# rel-ram-4x8K.net
KiCad netlist of a schematic drawn in EAGLE
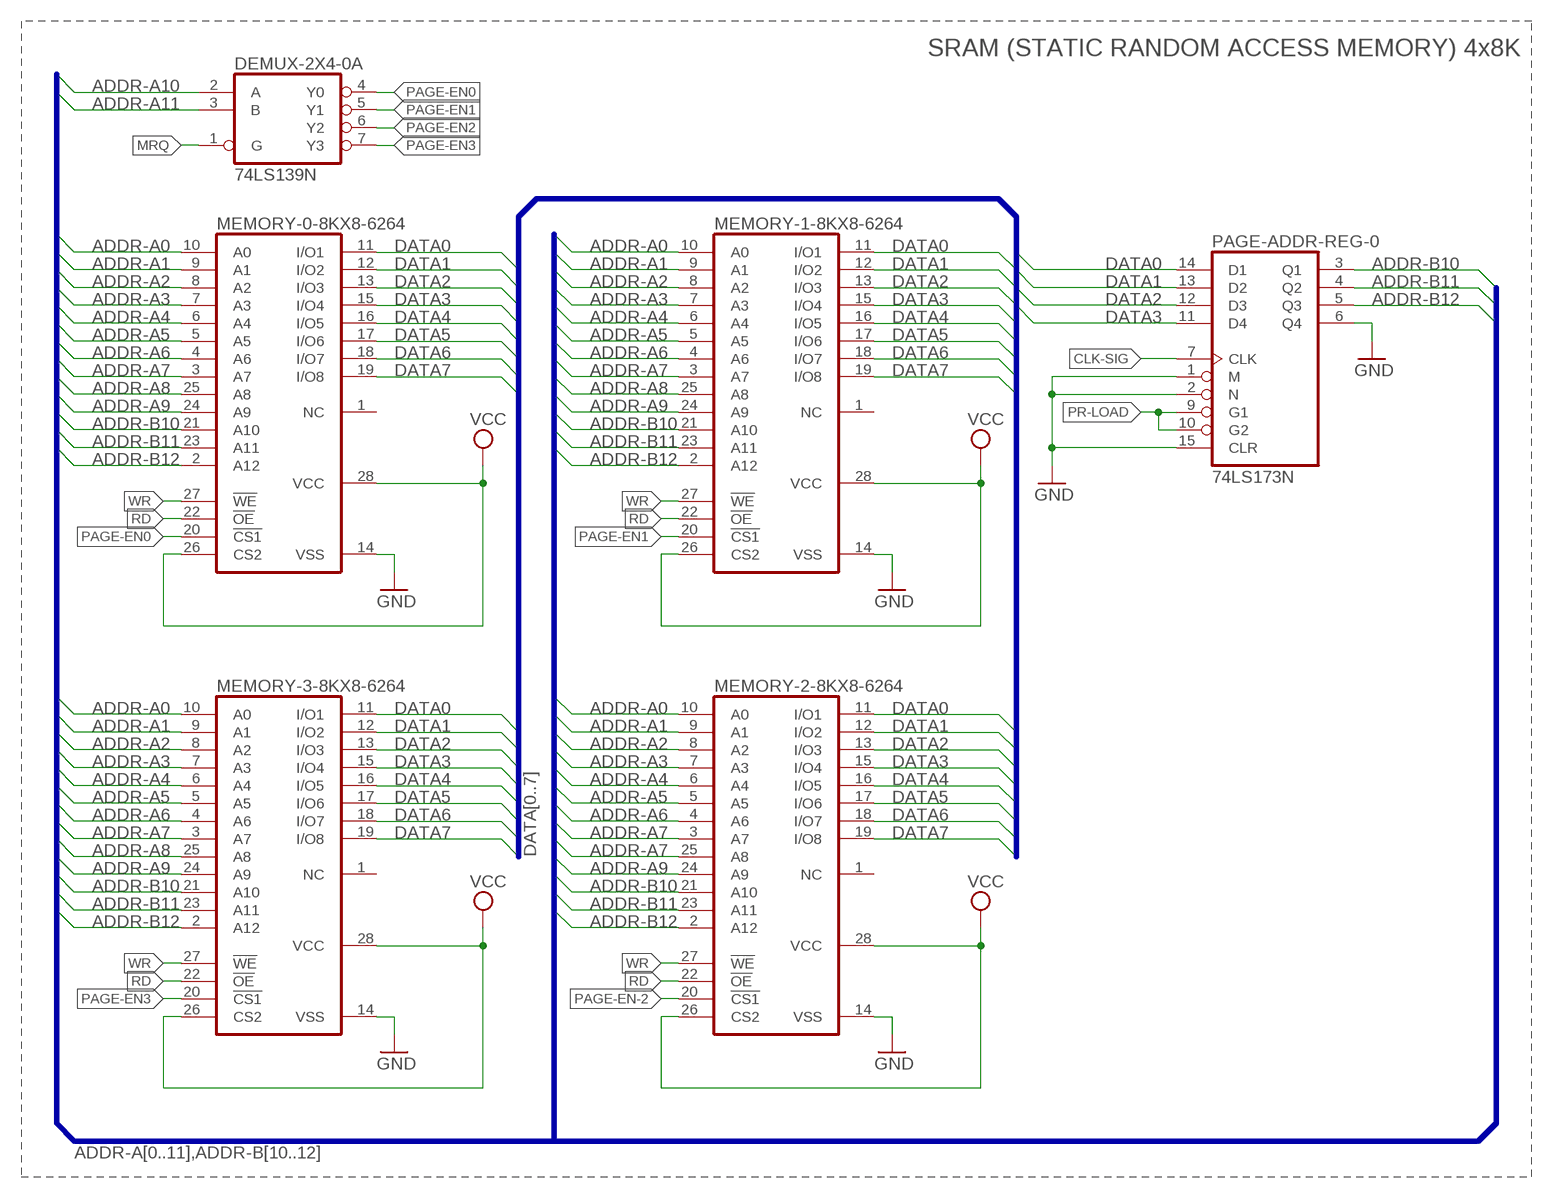
[diagram p0: schematic, sheet 1]

(export (version "E")
  (design (tool "Eeschema 10.0.6"))
  (components
    (comp (ref "DEMUX-2X4-0")
      (value "74LS139N")
      (footprint "eagle-import:DIL16")
      (libsource (lib "eagle-import") (part "74139NLS"))
    )
    (comp (ref "MEMORY-0-8KX8-6264")
      (value "6264A")
      (footprint "eagle-import:DIL28-6")
      (libsource (lib "eagle-import") (part "6264A"))
    )
    (comp (ref "MEMORY-1-8KX8-6264")
      (value "6264A")
      (footprint "eagle-import:DIL28-6")
      (libsource (lib "eagle-import") (part "6264A"))
    )
    (comp (ref "MEMORY-2-8KX8-6264")
      (value "6264A")
      (footprint "eagle-import:DIL28-6")
      (libsource (lib "eagle-import") (part "6264A"))
    )
    (comp (ref "MEMORY-3-8KX8-6264")
      (value "6264A")
      (footprint "eagle-import:DIL28-6")
      (libsource (lib "eagle-import") (part "6264A"))
    )
    (comp (ref "PAGE-ADDR-REG-0")
      (value "74LS173N")
      (footprint "eagle-import:DIL16")
      (libsource (lib "eagle-import") (part "74173NLS"))
    )
  )
  (nets
    (net (code "1") (name "/ADDR-A0") (class "Default")
      (node (ref "MEMORY-0-8KX8-6264") (pin "10") (pinfunction "A0_10") (pintype "input"))
      (node (ref "MEMORY-1-8KX8-6264") (pin "10") (pinfunction "A0_10") (pintype "input"))
      (node (ref "MEMORY-2-8KX8-6264") (pin "10") (pinfunction "A0_10") (pintype "input"))
      (node (ref "MEMORY-3-8KX8-6264") (pin "10") (pinfunction "A0_10") (pintype "input"))
    )
    (net (code "2") (name "/ADDR-A1") (class "Default")
      (node (ref "MEMORY-0-8KX8-6264") (pin "9") (pinfunction "A1_9") (pintype "input"))
      (node (ref "MEMORY-1-8KX8-6264") (pin "9") (pinfunction "A1_9") (pintype "input"))
      (node (ref "MEMORY-2-8KX8-6264") (pin "9") (pinfunction "A1_9") (pintype "input"))
      (node (ref "MEMORY-3-8KX8-6264") (pin "9") (pinfunction "A1_9") (pintype "input"))
    )
    (net (code "3") (name "/ADDR-A2") (class "Default")
      (node (ref "MEMORY-0-8KX8-6264") (pin "8") (pinfunction "A2_8") (pintype "input"))
      (node (ref "MEMORY-1-8KX8-6264") (pin "8") (pinfunction "A2_8") (pintype "input"))
      (node (ref "MEMORY-2-8KX8-6264") (pin "8") (pinfunction "A2_8") (pintype "input"))
      (node (ref "MEMORY-3-8KX8-6264") (pin "8") (pinfunction "A2_8") (pintype "input"))
    )
    (net (code "4") (name "/ADDR-A3") (class "Default")
      (node (ref "MEMORY-0-8KX8-6264") (pin "7") (pinfunction "A3_7") (pintype "input"))
      (node (ref "MEMORY-1-8KX8-6264") (pin "7") (pinfunction "A3_7") (pintype "input"))
      (node (ref "MEMORY-2-8KX8-6264") (pin "7") (pinfunction "A3_7") (pintype "input"))
      (node (ref "MEMORY-3-8KX8-6264") (pin "7") (pinfunction "A3_7") (pintype "input"))
    )
    (net (code "5") (name "/ADDR-A4") (class "Default")
      (node (ref "MEMORY-0-8KX8-6264") (pin "6") (pinfunction "A4_6") (pintype "input"))
      (node (ref "MEMORY-1-8KX8-6264") (pin "6") (pinfunction "A4_6") (pintype "input"))
      (node (ref "MEMORY-2-8KX8-6264") (pin "6") (pinfunction "A4_6") (pintype "input"))
      (node (ref "MEMORY-3-8KX8-6264") (pin "6") (pinfunction "A4_6") (pintype "input"))
    )
    (net (code "6") (name "/ADDR-A5") (class "Default")
      (node (ref "MEMORY-0-8KX8-6264") (pin "5") (pinfunction "A5_5") (pintype "input"))
      (node (ref "MEMORY-1-8KX8-6264") (pin "5") (pinfunction "A5_5") (pintype "input"))
      (node (ref "MEMORY-2-8KX8-6264") (pin "5") (pinfunction "A5_5") (pintype "input"))
      (node (ref "MEMORY-3-8KX8-6264") (pin "5") (pinfunction "A5_5") (pintype "input"))
    )
    (net (code "7") (name "/ADDR-A6") (class "Default")
      (node (ref "MEMORY-0-8KX8-6264") (pin "4") (pinfunction "A6_4") (pintype "input"))
      (node (ref "MEMORY-1-8KX8-6264") (pin "4") (pinfunction "A6_4") (pintype "input"))
      (node (ref "MEMORY-2-8KX8-6264") (pin "4") (pinfunction "A6_4") (pintype "input"))
      (node (ref "MEMORY-3-8KX8-6264") (pin "4") (pinfunction "A6_4") (pintype "input"))
    )
    (net (code "8") (name "/ADDR-A7") (class "Default")
      (node (ref "MEMORY-0-8KX8-6264") (pin "3") (pinfunction "A7_3") (pintype "input"))
      (node (ref "MEMORY-1-8KX8-6264") (pin "3") (pinfunction "A7_3") (pintype "input"))
      (node (ref "MEMORY-2-8KX8-6264") (pin "25") (pinfunction "A8_25") (pintype "input"))
      (node (ref "MEMORY-2-8KX8-6264") (pin "3") (pinfunction "A7_3") (pintype "input"))
      (node (ref "MEMORY-3-8KX8-6264") (pin "3") (pinfunction "A7_3") (pintype "input"))
    )
    (net (code "9") (name "/ADDR-A8") (class "Default")
      (node (ref "MEMORY-0-8KX8-6264") (pin "25") (pinfunction "A8_25") (pintype "input"))
      (node (ref "MEMORY-1-8KX8-6264") (pin "25") (pinfunction "A8_25") (pintype "input"))
      (node (ref "MEMORY-3-8KX8-6264") (pin "25") (pinfunction "A8_25") (pintype "input"))
    )
    (net (code "10") (name "/ADDR-A9") (class "Default")
      (node (ref "MEMORY-0-8KX8-6264") (pin "24") (pinfunction "A9_24") (pintype "input"))
      (node (ref "MEMORY-1-8KX8-6264") (pin "24") (pinfunction "A9_24") (pintype "input"))
      (node (ref "MEMORY-2-8KX8-6264") (pin "24") (pinfunction "A9_24") (pintype "input"))
      (node (ref "MEMORY-3-8KX8-6264") (pin "24") (pinfunction "A9_24") (pintype "input"))
    )
    (net (code "11") (name "/ADDR-A10") (class "Default")
      (node (ref "DEMUX-2X4-0") (pin "2") (pinfunction "A_2") (pintype "input"))
    )
    (net (code "12") (name "/ADDR-A11") (class "Default")
      (node (ref "DEMUX-2X4-0") (pin "3") (pinfunction "B_3") (pintype "input"))
    )
    (net (code "13") (name "/ADDR-B10") (class "Default")
      (node (ref "MEMORY-0-8KX8-6264") (pin "21") (pinfunction "A10_21") (pintype "input"))
      (node (ref "MEMORY-1-8KX8-6264") (pin "21") (pinfunction "A10_21") (pintype "input"))
      (node (ref "MEMORY-2-8KX8-6264") (pin "21") (pinfunction "A10_21") (pintype "input"))
      (node (ref "MEMORY-3-8KX8-6264") (pin "21") (pinfunction "A10_21") (pintype "input"))
      (node (ref "PAGE-ADDR-REG-0") (pin "3") (pinfunction "Q1_3") (pintype "tri_state"))
    )
    (net (code "14") (name "/ADDR-B11") (class "Default")
      (node (ref "MEMORY-0-8KX8-6264") (pin "23") (pinfunction "A11_23") (pintype "input"))
      (node (ref "MEMORY-1-8KX8-6264") (pin "23") (pinfunction "A11_23") (pintype "input"))
      (node (ref "MEMORY-2-8KX8-6264") (pin "23") (pinfunction "A11_23") (pintype "input"))
      (node (ref "MEMORY-3-8KX8-6264") (pin "23") (pinfunction "A11_23") (pintype "input"))
      (node (ref "PAGE-ADDR-REG-0") (pin "4") (pinfunction "Q2_4") (pintype "tri_state"))
    )
    (net (code "15") (name "/ADDR-B12") (class "Default")
      (node (ref "MEMORY-0-8KX8-6264") (pin "2") (pinfunction "A12_2") (pintype "input"))
      (node (ref "MEMORY-1-8KX8-6264") (pin "2") (pinfunction "A12_2") (pintype "input"))
      (node (ref "MEMORY-2-8KX8-6264") (pin "2") (pinfunction "A12_2") (pintype "input"))
      (node (ref "MEMORY-3-8KX8-6264") (pin "2") (pinfunction "A12_2") (pintype "input"))
      (node (ref "PAGE-ADDR-REG-0") (pin "5") (pinfunction "Q3_5") (pintype "tri_state"))
    )
    (net (code "16") (name "/DATA0") (class "Default")
      (node (ref "MEMORY-0-8KX8-6264") (pin "11") (pinfunction "I/O1_11") (pintype "bidirectional"))
      (node (ref "MEMORY-1-8KX8-6264") (pin "11") (pinfunction "I/O1_11") (pintype "bidirectional"))
      (node (ref "MEMORY-2-8KX8-6264") (pin "11") (pinfunction "I/O1_11") (pintype "bidirectional"))
      (node (ref "MEMORY-3-8KX8-6264") (pin "11") (pinfunction "I/O1_11") (pintype "bidirectional"))
      (node (ref "PAGE-ADDR-REG-0") (pin "14") (pinfunction "D1_14") (pintype "input"))
    )
    (net (code "17") (name "/DATA1") (class "Default")
      (node (ref "MEMORY-0-8KX8-6264") (pin "12") (pinfunction "I/O2_12") (pintype "bidirectional"))
      (node (ref "MEMORY-1-8KX8-6264") (pin "12") (pinfunction "I/O2_12") (pintype "bidirectional"))
      (node (ref "MEMORY-2-8KX8-6264") (pin "12") (pinfunction "I/O2_12") (pintype "bidirectional"))
      (node (ref "MEMORY-3-8KX8-6264") (pin "12") (pinfunction "I/O2_12") (pintype "bidirectional"))
      (node (ref "PAGE-ADDR-REG-0") (pin "13") (pinfunction "D2_13") (pintype "input"))
    )
    (net (code "18") (name "/DATA2") (class "Default")
      (node (ref "MEMORY-0-8KX8-6264") (pin "13") (pinfunction "I/O3_13") (pintype "bidirectional"))
      (node (ref "MEMORY-1-8KX8-6264") (pin "13") (pinfunction "I/O3_13") (pintype "bidirectional"))
      (node (ref "MEMORY-2-8KX8-6264") (pin "13") (pinfunction "I/O3_13") (pintype "bidirectional"))
      (node (ref "MEMORY-3-8KX8-6264") (pin "13") (pinfunction "I/O3_13") (pintype "bidirectional"))
      (node (ref "PAGE-ADDR-REG-0") (pin "12") (pinfunction "D3_12") (pintype "input"))
    )
    (net (code "19") (name "/DATA3") (class "Default")
      (node (ref "MEMORY-0-8KX8-6264") (pin "15") (pinfunction "I/O4_15") (pintype "bidirectional"))
      (node (ref "MEMORY-1-8KX8-6264") (pin "15") (pinfunction "I/O4_15") (pintype "bidirectional"))
      (node (ref "MEMORY-2-8KX8-6264") (pin "15") (pinfunction "I/O4_15") (pintype "bidirectional"))
      (node (ref "MEMORY-3-8KX8-6264") (pin "15") (pinfunction "I/O4_15") (pintype "bidirectional"))
      (node (ref "PAGE-ADDR-REG-0") (pin "11") (pinfunction "D4_11") (pintype "input"))
    )
    (net (code "20") (name "/DATA4") (class "Default")
      (node (ref "MEMORY-0-8KX8-6264") (pin "16") (pinfunction "I/O5_16") (pintype "bidirectional"))
      (node (ref "MEMORY-1-8KX8-6264") (pin "16") (pinfunction "I/O5_16") (pintype "bidirectional"))
      (node (ref "MEMORY-2-8KX8-6264") (pin "16") (pinfunction "I/O5_16") (pintype "bidirectional"))
      (node (ref "MEMORY-3-8KX8-6264") (pin "16") (pinfunction "I/O5_16") (pintype "bidirectional"))
    )
    (net (code "21") (name "/DATA5") (class "Default")
      (node (ref "MEMORY-0-8KX8-6264") (pin "17") (pinfunction "I/O6_17") (pintype "bidirectional"))
      (node (ref "MEMORY-1-8KX8-6264") (pin "17") (pinfunction "I/O6_17") (pintype "bidirectional"))
      (node (ref "MEMORY-2-8KX8-6264") (pin "17") (pinfunction "I/O6_17") (pintype "bidirectional"))
      (node (ref "MEMORY-3-8KX8-6264") (pin "17") (pinfunction "I/O6_17") (pintype "bidirectional"))
    )
    (net (code "22") (name "/DATA6") (class "Default")
      (node (ref "MEMORY-0-8KX8-6264") (pin "18") (pinfunction "I/O7_18") (pintype "bidirectional"))
      (node (ref "MEMORY-1-8KX8-6264") (pin "18") (pinfunction "I/O7_18") (pintype "bidirectional"))
      (node (ref "MEMORY-2-8KX8-6264") (pin "18") (pinfunction "I/O7_18") (pintype "bidirectional"))
      (node (ref "MEMORY-3-8KX8-6264") (pin "18") (pinfunction "I/O7_18") (pintype "bidirectional"))
    )
    (net (code "23") (name "/DATA7") (class "Default")
      (node (ref "MEMORY-0-8KX8-6264") (pin "19") (pinfunction "I/O8_19") (pintype "bidirectional"))
      (node (ref "MEMORY-1-8KX8-6264") (pin "19") (pinfunction "I/O8_19") (pintype "bidirectional"))
      (node (ref "MEMORY-2-8KX8-6264") (pin "19") (pinfunction "I/O8_19") (pintype "bidirectional"))
      (node (ref "MEMORY-3-8KX8-6264") (pin "19") (pinfunction "I/O8_19") (pintype "bidirectional"))
    )
    (net (code "26") (name "CLK-SIG") (class "Default")
      (node (ref "PAGE-ADDR-REG-0") (pin "7") (pinfunction "CLK_7") (pintype "input"))
    )
    (net (code "27") (name "GND") (class "Default")
      (node (ref "MEMORY-0-8KX8-6264") (pin "14") (pinfunction "VSS_14") (pintype "power_in"))
      (node (ref "MEMORY-1-8KX8-6264") (pin "14") (pinfunction "VSS_14") (pintype "power_in"))
      (node (ref "MEMORY-2-8KX8-6264") (pin "14") (pinfunction "VSS_14") (pintype "power_in"))
      (node (ref "MEMORY-3-8KX8-6264") (pin "14") (pinfunction "VSS_14") (pintype "power_in"))
      (node (ref "PAGE-ADDR-REG-0") (pin "1") (pinfunction "M_1") (pintype "input"))
      (node (ref "PAGE-ADDR-REG-0") (pin "15") (pinfunction "CLR_15") (pintype "input"))
      (node (ref "PAGE-ADDR-REG-0") (pin "2") (pinfunction "N_2") (pintype "input"))
      (node (ref "PAGE-ADDR-REG-0") (pin "6") (pinfunction "Q4_6") (pintype "tri_state"))
    )
    (net (code "28") (name "MRQ") (class "Default")
      (node (ref "DEMUX-2X4-0") (pin "1") (pinfunction "G_1") (pintype "input"))
    )
    (net (code "29") (name "PAGE-EN-2") (class "Default")
      (node (ref "MEMORY-2-8KX8-6264") (pin "20") (pinfunction "~{CS1}_20") (pintype "input"))
    )
    (net (code "30") (name "PAGE-EN0") (class "Default")
      (node (ref "DEMUX-2X4-0") (pin "4") (pinfunction "Y0_4") (pintype "output"))
      (node (ref "MEMORY-0-8KX8-6264") (pin "20") (pinfunction "~{CS1}_20") (pintype "input"))
    )
    (net (code "31") (name "PAGE-EN1") (class "Default")
      (node (ref "DEMUX-2X4-0") (pin "5") (pinfunction "Y1_5") (pintype "output"))
      (node (ref "MEMORY-1-8KX8-6264") (pin "20") (pinfunction "~{CS1}_20") (pintype "input"))
    )
    (net (code "32") (name "PAGE-EN2") (class "Default")
      (node (ref "DEMUX-2X4-0") (pin "6") (pinfunction "Y2_6") (pintype "output"))
    )
    (net (code "33") (name "PAGE-EN3") (class "Default")
      (node (ref "DEMUX-2X4-0") (pin "7") (pinfunction "Y3_7") (pintype "output"))
      (node (ref "MEMORY-3-8KX8-6264") (pin "20") (pinfunction "~{CS1}_20") (pintype "input"))
    )
    (net (code "34") (name "PR-LOAD") (class "Default")
      (node (ref "PAGE-ADDR-REG-0") (pin "10") (pinfunction "G2_10") (pintype "input"))
      (node (ref "PAGE-ADDR-REG-0") (pin "9") (pinfunction "G1_9") (pintype "input"))
    )
    (net (code "35") (name "RD") (class "Default")
      (node (ref "MEMORY-0-8KX8-6264") (pin "22") (pinfunction "~{OE}_22") (pintype "input"))
      (node (ref "MEMORY-1-8KX8-6264") (pin "22") (pinfunction "~{OE}_22") (pintype "input"))
      (node (ref "MEMORY-2-8KX8-6264") (pin "22") (pinfunction "~{OE}_22") (pintype "input"))
      (node (ref "MEMORY-3-8KX8-6264") (pin "22") (pinfunction "~{OE}_22") (pintype "input"))
    )
    (net (code "36") (name "VCC") (class "Default")
      (node (ref "MEMORY-0-8KX8-6264") (pin "26") (pinfunction "CS2_26") (pintype "input"))
      (node (ref "MEMORY-0-8KX8-6264") (pin "28") (pinfunction "VCC_28") (pintype "power_in"))
      (node (ref "MEMORY-1-8KX8-6264") (pin "26") (pinfunction "CS2_26") (pintype "input"))
      (node (ref "MEMORY-1-8KX8-6264") (pin "28") (pinfunction "VCC_28") (pintype "power_in"))
      (node (ref "MEMORY-2-8KX8-6264") (pin "26") (pinfunction "CS2_26") (pintype "input"))
      (node (ref "MEMORY-2-8KX8-6264") (pin "28") (pinfunction "VCC_28") (pintype "power_in"))
      (node (ref "MEMORY-3-8KX8-6264") (pin "26") (pinfunction "CS2_26") (pintype "input"))
      (node (ref "MEMORY-3-8KX8-6264") (pin "28") (pinfunction "VCC_28") (pintype "power_in"))
    )
    (net (code "37") (name "WR") (class "Default")
      (node (ref "MEMORY-0-8KX8-6264") (pin "27") (pinfunction "~{WE}_27") (pintype "input"))
      (node (ref "MEMORY-1-8KX8-6264") (pin "27") (pinfunction "~{WE}_27") (pintype "input"))
      (node (ref "MEMORY-2-8KX8-6264") (pin "27") (pinfunction "~{WE}_27") (pintype "input"))
      (node (ref "MEMORY-3-8KX8-6264") (pin "27") (pinfunction "~{WE}_27") (pintype "input"))
    )
    (net (code "38") (name "unconnected-(MEMORY-0-8KX8-6264-NC-Pad1)") (class "Default")
      (node (ref "MEMORY-0-8KX8-6264") (pin "1") (pinfunction "NC_1") (pintype "no_connect"))
    )
    (net (code "39") (name "unconnected-(MEMORY-1-8KX8-6264-NC-Pad1)") (class "Default")
      (node (ref "MEMORY-1-8KX8-6264") (pin "1") (pinfunction "NC_1") (pintype "no_connect"))
    )
    (net (code "40") (name "unconnected-(MEMORY-2-8KX8-6264-NC-Pad1)") (class "Default")
      (node (ref "MEMORY-2-8KX8-6264") (pin "1") (pinfunction "NC_1") (pintype "no_connect"))
    )
    (net (code "41") (name "unconnected-(MEMORY-3-8KX8-6264-NC-Pad1)") (class "Default")
      (node (ref "MEMORY-3-8KX8-6264") (pin "1") (pinfunction "NC_1") (pintype "no_connect"))
    )
  )
)
